# Display_LCD16x2.net
KiCad netlist of a schematic drawn in Altium Designer
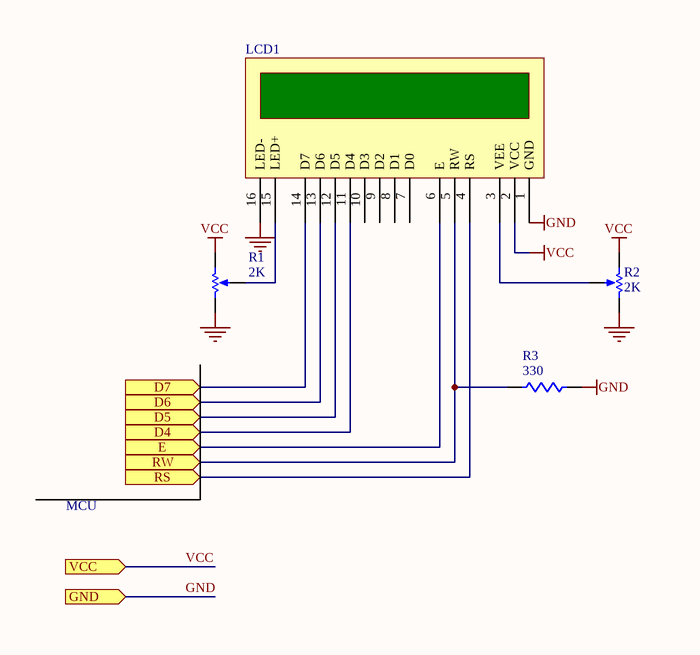
[diagram p0: Display_LCD16x2.SchDoc]

(export (version "E")
  (design (tool "Eeschema 10.0.6"))
  (components
    (comp (ref "LCD1")
      (value "LCD_16*2")
      (footprint "LCD_2x16")
      (libsource (lib "Miscellaneous Devices") (part "LCD_16*2"))
    )
    (comp (ref "R1")
      (value "2K")
      (footprint "VR8-5/5.6MM")
      (description "Potentiometer")
      (fields
        (field (name "MANUFACTURER") "Generic Components")
        (field (name "Comment") "RPot1")
        (field (name "PUBLISHER") "Altium Limited")
      )
      (libsource (lib "Miscellaneous Devices") (part "RPot1"))
    )
    (comp (ref "R2")
      (value "2K")
      (footprint "VR8-5/5.6MM")
      (description "Potentiometer")
      (fields
        (field (name "MANUFACTURER") "Generic Components")
        (field (name "Comment") "RPot1")
        (field (name "PUBLISHER") "Altium Limited")
      )
      (libsource (lib "Miscellaneous Devices") (part "RPot1"))
    )
    (comp (ref "R3")
      (value "330")
      (footprint "AXIAL-0.4")
      (description "Resistor")
      (fields
        (field (name "MANUFACTURER") "Generic Components")
        (field (name "Comment") "Res1")
        (field (name "PUBLISHER") "Altium Limited")
      )
      (libsource (lib "Miscellaneous Devices") (part "Res1"))
    )
  )
  (nets
    (net (code "1") (name "/D4") (class "Default")
      (node (ref "LCD1") (pin "11") (pinfunction "D4_11") (pintype "passive"))
    )
    (net (code "2") (name "/D5") (class "Default")
      (node (ref "LCD1") (pin "12") (pinfunction "D5_12") (pintype "passive"))
    )
    (net (code "3") (name "/D6") (class "Default")
      (node (ref "LCD1") (pin "13") (pinfunction "D6_13") (pintype "passive"))
    )
    (net (code "4") (name "/D7") (class "Default")
      (node (ref "LCD1") (pin "14") (pinfunction "D7_14") (pintype "passive"))
    )
    (net (code "5") (name "/E") (class "Default")
      (node (ref "LCD1") (pin "6") (pinfunction "E_6") (pintype "passive"))
    )
    (net (code "6") (name "/RS") (class "Default")
      (node (ref "LCD1") (pin "4") (pinfunction "RS_4") (pintype "passive"))
    )
    (net (code "7") (name "/RW") (class "Default")
      (node (ref "LCD1") (pin "5") (pinfunction "RW_5") (pintype "passive"))
      (node (ref "R3") (pin "2") (pinfunction "2_2") (pintype "passive"))
    )
    (net (code "8") (name "GND") (class "Default")
      (node (ref "LCD1") (pin "1") (pinfunction "GND_1") (pintype "passive"))
      (node (ref "LCD1") (pin "16") (pinfunction "LED-_16") (pintype "passive"))
      (node (ref "R1") (pin "2") (pinfunction "BOT_2") (pintype "passive"))
      (node (ref "R2") (pin "1") (pinfunction "TOP_1") (pintype "passive"))
      (node (ref "R3") (pin "1") (pinfunction "1_1") (pintype "passive"))
    )
    (net (code "9") (name "Net-(LCD1-LED+)") (class "Default")
      (node (ref "LCD1") (pin "15") (pinfunction "LED+_15") (pintype "passive"))
      (node (ref "R1") (pin "3") (pinfunction "TAP_3") (pintype "passive"))
    )
    (net (code "10") (name "Net-(LCD1-VEE)") (class "Default")
      (node (ref "LCD1") (pin "3") (pinfunction "VEE_3") (pintype "passive"))
      (node (ref "R2") (pin "3") (pinfunction "TAP_3") (pintype "passive"))
    )
    (net (code "11") (name "VCC") (class "Default")
      (node (ref "LCD1") (pin "2") (pinfunction "VCC_2") (pintype "passive"))
      (node (ref "R1") (pin "1") (pinfunction "TOP_1") (pintype "passive"))
      (node (ref "R2") (pin "2") (pinfunction "BOT_2") (pintype "passive"))
    )
    (net (code "12") (name "unconnected-(LCD1-D0-Pad7)") (class "Default")
      (node (ref "LCD1") (pin "7") (pinfunction "D0_7") (pintype "passive"))
    )
    (net (code "13") (name "unconnected-(LCD1-D1-Pad8)") (class "Default")
      (node (ref "LCD1") (pin "8") (pinfunction "D1_8") (pintype "passive"))
    )
    (net (code "14") (name "unconnected-(LCD1-D2-Pad9)") (class "Default")
      (node (ref "LCD1") (pin "9") (pinfunction "D2_9") (pintype "passive"))
    )
    (net (code "15") (name "unconnected-(LCD1-D3-Pad10)") (class "Default")
      (node (ref "LCD1") (pin "10") (pinfunction "D3_10") (pintype "passive"))
    )
  )
)
